# SpectrumPlusKeyboard_Kombi.net
KiCad netlist of a schematic drawn in EAGLE
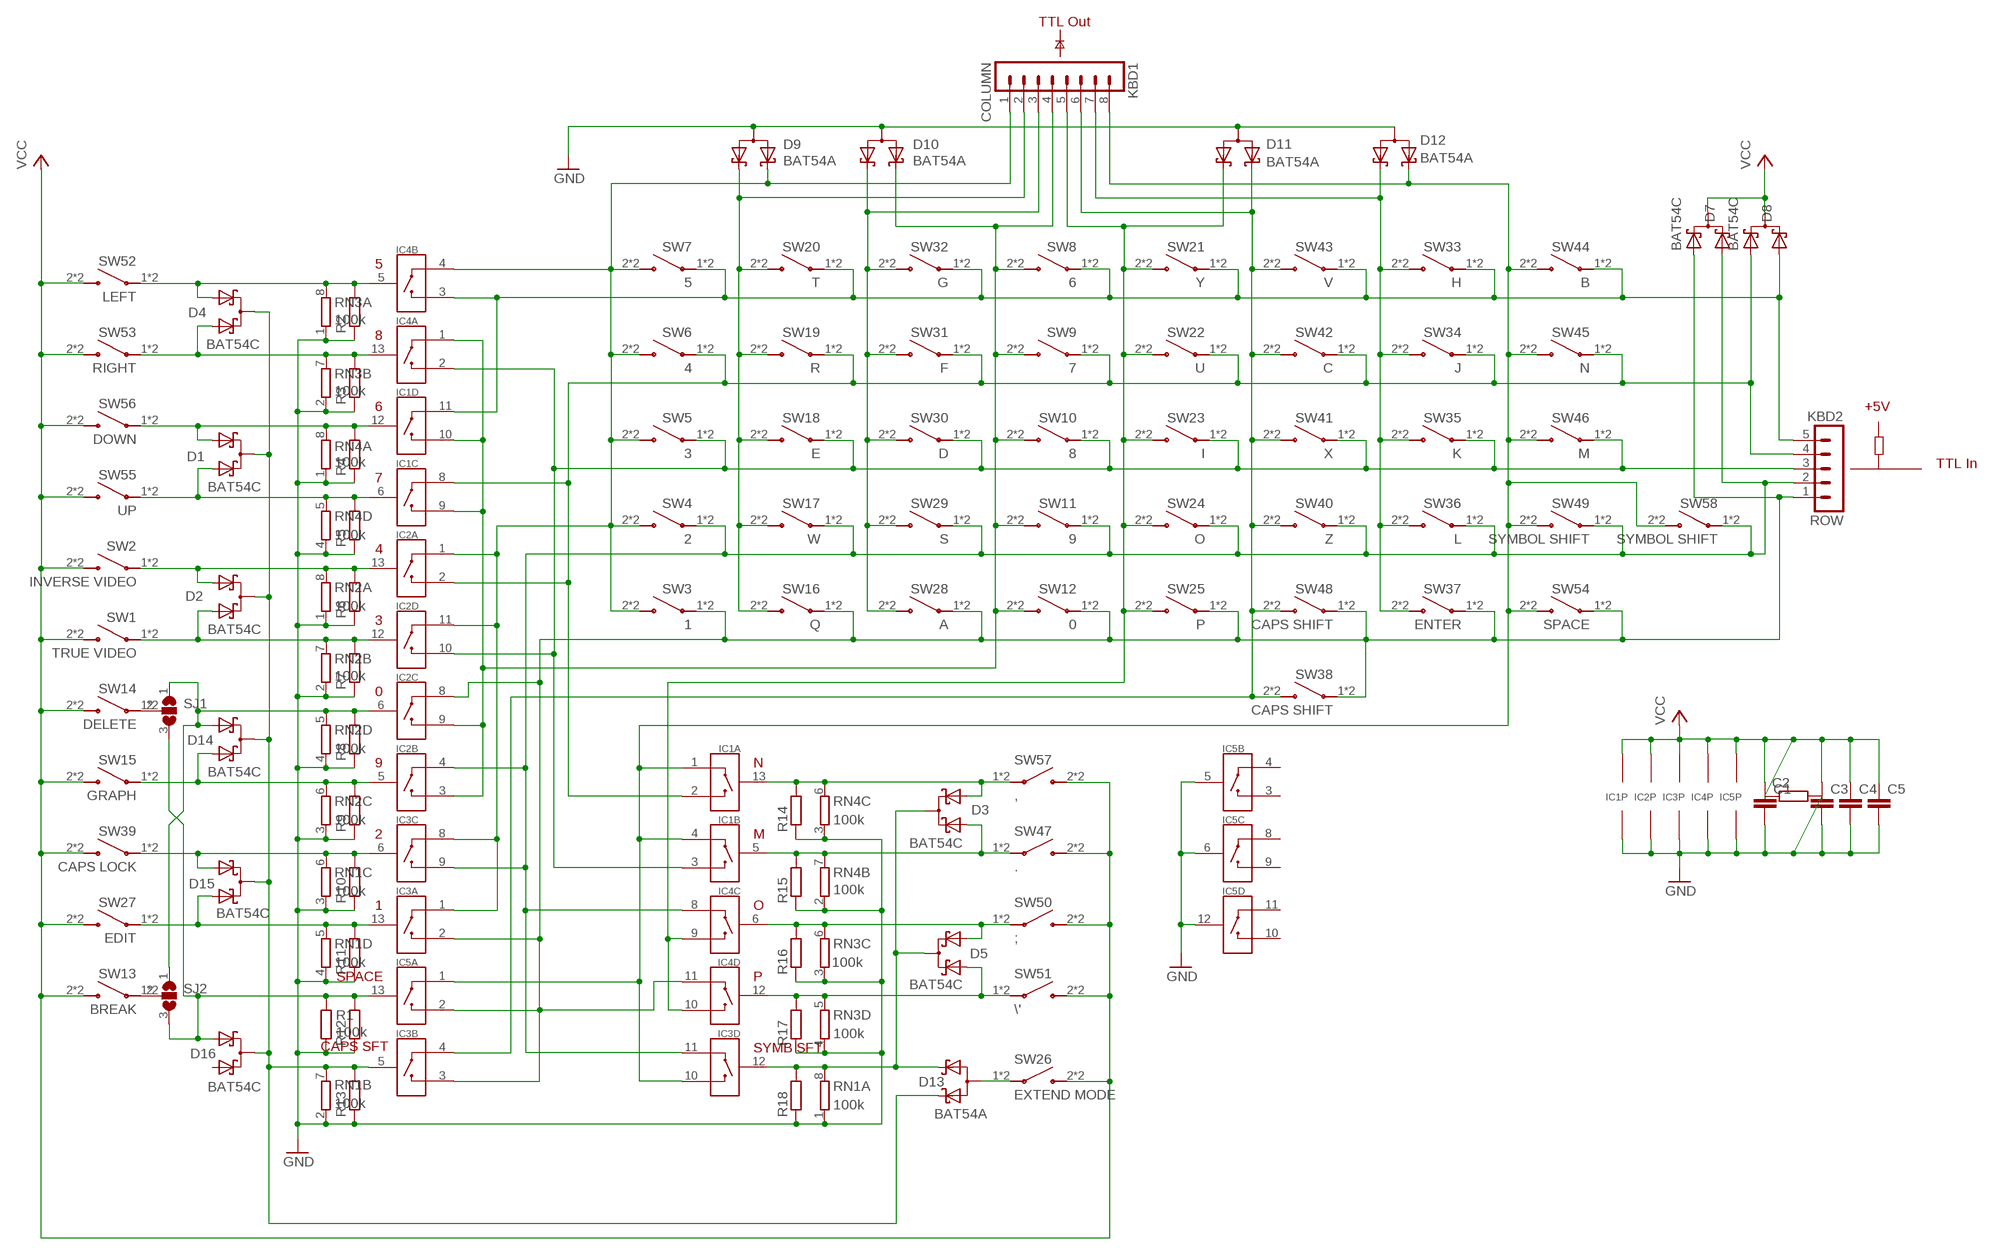
[diagram p0: schematic, sheet 1]

(export (version "E")
  (design (tool "Eeschema 10.0.6"))
  (components
    (comp (ref "C1")
      (value "C-EUC0805")
      (footprint "eagle-import:C0805")
      (libsource (lib "eagle-import") (part "C-EUC0805"))
    )
    (comp (ref "C2")
      (value "R-EU_R0805")
      (footprint "eagle-import:R0805")
      (libsource (lib "eagle-import") (part "R-EU_R0805"))
    )
    (comp (ref "C3")
      (value "C-EUC0805")
      (footprint "eagle-import:C0805")
      (libsource (lib "eagle-import") (part "C-EUC0805"))
    )
    (comp (ref "C4")
      (value "C-EUC0805")
      (footprint "eagle-import:C0805")
      (libsource (lib "eagle-import") (part "C-EUC0805"))
    )
    (comp (ref "C5")
      (value "C-EUC0805")
      (footprint "eagle-import:C0805")
      (libsource (lib "eagle-import") (part "C-EUC0805"))
    )
    (comp (ref "D1")
      (value "BAT54C")
      (footprint "eagle-import:SOT-23")
      (libsource (lib "eagle-import") (part "BAT54C"))
    )
    (comp (ref "D2")
      (value "BAT54C")
      (footprint "eagle-import:SOT-23")
      (libsource (lib "eagle-import") (part "BAT54C"))
    )
    (comp (ref "D3")
      (value "BAT54C")
      (footprint "eagle-import:SOT-23")
      (libsource (lib "eagle-import") (part "BAT54C"))
    )
    (comp (ref "D4")
      (value "BAT54C")
      (footprint "eagle-import:SOT-23")
      (libsource (lib "eagle-import") (part "BAT54C"))
    )
    (comp (ref "D5")
      (value "BAT54C")
      (footprint "eagle-import:SOT-23")
      (libsource (lib "eagle-import") (part "BAT54C"))
    )
    (comp (ref "D7")
      (value "BAT54C")
      (footprint "eagle-import:SOT-23")
      (libsource (lib "eagle-import") (part "BAT54C"))
    )
    (comp (ref "D8")
      (value "BAT54C")
      (footprint "eagle-import:SOT-23")
      (libsource (lib "eagle-import") (part "BAT54C"))
    )
    (comp (ref "D9")
      (value "BAT54A")
      (footprint "eagle-import:SOT-23")
      (libsource (lib "eagle-import") (part "BAT54A"))
    )
    (comp (ref "D10")
      (value "BAT54A")
      (footprint "eagle-import:SOT-23")
      (libsource (lib "eagle-import") (part "BAT54A"))
    )
    (comp (ref "D11")
      (value "BAT54A")
      (footprint "eagle-import:SOT-23")
      (libsource (lib "eagle-import") (part "BAT54A"))
    )
    (comp (ref "D12")
      (value "BAT54A")
      (footprint "eagle-import:SOT-23")
      (libsource (lib "eagle-import") (part "BAT54A"))
    )
    (comp (ref "D13")
      (value "BAT54A")
      (footprint "eagle-import:SOT-23")
      (libsource (lib "eagle-import") (part "BAT54A"))
    )
    (comp (ref "D14")
      (value "BAT54C")
      (footprint "eagle-import:SOT-23")
      (libsource (lib "eagle-import") (part "BAT54C"))
    )
    (comp (ref "D15")
      (value "BAT54C")
      (footprint "eagle-import:SOT-23")
      (libsource (lib "eagle-import") (part "BAT54C"))
    )
    (comp (ref "D16")
      (value "BAT54C")
      (footprint "eagle-import:SOT-23")
      (libsource (lib "eagle-import") (part "BAT54C"))
    )
    (comp (ref "IC1")
      (value "4066")
      (footprint "eagle-import:SO14")
      (libsource (lib "eagle-import") (part "4066"))
    )
    (comp (ref "IC2")
      (value "4066")
      (footprint "eagle-import:SO14")
      (libsource (lib "eagle-import") (part "4066"))
    )
    (comp (ref "IC3")
      (value "4066")
      (footprint "eagle-import:SO14")
      (libsource (lib "eagle-import") (part "4066"))
    )
    (comp (ref "IC4")
      (value "4066")
      (footprint "eagle-import:SO14")
      (libsource (lib "eagle-import") (part "4066"))
    )
    (comp (ref "IC5")
      (value "4066")
      (footprint "eagle-import:SO14")
      (libsource (lib "eagle-import") (part "4066"))
    )
    (comp (ref "KBD1")
      (value "COLUMN")
      (footprint "eagle-import:MA08-1")
      (libsource (lib "eagle-import") (part "MA08-1"))
    )
    (comp (ref "KBD2")
      (value "ROW")
      (footprint "eagle-import:MA05-1")
      (libsource (lib "eagle-import") (part "MA05-1"))
    )
    (comp (ref "R1")
      (value "100k")
      (footprint "eagle-import:R0805")
      (libsource (lib "eagle-import") (part "R-EU_R0805"))
    )
    (comp (ref "R2")
      (value "R-EU_R0805")
      (footprint "eagle-import:R0805")
      (libsource (lib "eagle-import") (part "R-EU_R0805"))
    )
    (comp (ref "R3")
      (value "R-EU_R0805")
      (footprint "eagle-import:R0805")
      (libsource (lib "eagle-import") (part "R-EU_R0805"))
    )
    (comp (ref "R4")
      (value "R-EU_R0805")
      (footprint "eagle-import:R0805")
      (libsource (lib "eagle-import") (part "R-EU_R0805"))
    )
    (comp (ref "R5")
      (value "R-EU_R0805")
      (footprint "eagle-import:R0805")
      (libsource (lib "eagle-import") (part "R-EU_R0805"))
    )
    (comp (ref "R6")
      (value "R-EU_R0805")
      (footprint "eagle-import:R0805")
      (libsource (lib "eagle-import") (part "R-EU_R0805"))
    )
    (comp (ref "R7")
      (value "R-EU_R0805")
      (footprint "eagle-import:R0805")
      (libsource (lib "eagle-import") (part "R-EU_R0805"))
    )
    (comp (ref "R8")
      (value "R-EU_R0805")
      (footprint "eagle-import:R0805")
      (libsource (lib "eagle-import") (part "R-EU_R0805"))
    )
    (comp (ref "R9")
      (value "R-EU_R0805")
      (footprint "eagle-import:R0805")
      (libsource (lib "eagle-import") (part "R-EU_R0805"))
    )
    (comp (ref "R10")
      (value "R-EU_R0805")
      (footprint "eagle-import:R0805")
      (libsource (lib "eagle-import") (part "R-EU_R0805"))
    )
    (comp (ref "R11")
      (value "R-EU_R0805")
      (footprint "eagle-import:R0805")
      (libsource (lib "eagle-import") (part "R-EU_R0805"))
    )
    (comp (ref "R12")
      (value "R-EU_R0805")
      (footprint "eagle-import:R0805")
      (libsource (lib "eagle-import") (part "R-EU_R0805"))
    )
    (comp (ref "R13")
      (value "R-EU_R0805")
      (footprint "eagle-import:R0805")
      (libsource (lib "eagle-import") (part "R-EU_R0805"))
    )
    (comp (ref "R14")
      (value "R-EU_R0805")
      (footprint "eagle-import:R0805")
      (libsource (lib "eagle-import") (part "R-EU_R0805"))
    )
    (comp (ref "R15")
      (value "R-EU_R0805")
      (footprint "eagle-import:R0805")
      (libsource (lib "eagle-import") (part "R-EU_R0805"))
    )
    (comp (ref "R16")
      (value "R-EU_R0805")
      (footprint "eagle-import:R0805")
      (libsource (lib "eagle-import") (part "R-EU_R0805"))
    )
    (comp (ref "R17")
      (value "R-EU_R0805")
      (footprint "eagle-import:R0805")
      (libsource (lib "eagle-import") (part "R-EU_R0805"))
    )
    (comp (ref "R18")
      (value "R-EU_R0805")
      (footprint "eagle-import:R0805")
      (libsource (lib "eagle-import") (part "R-EU_R0805"))
    )
    (comp (ref "RN1")
      (value "100k")
      (footprint "eagle-import:0603-ARC")
      (libsource (lib "eagle-import") (part "4R-N0603-ARC"))
    )
    (comp (ref "RN2")
      (value "100k")
      (footprint "eagle-import:0603-ARC")
      (libsource (lib "eagle-import") (part "4R-N0603-ARC"))
    )
    (comp (ref "RN3")
      (value "100k")
      (footprint "eagle-import:0603-ARC")
      (libsource (lib "eagle-import") (part "4R-N0603-ARC"))
    )
    (comp (ref "RN4")
      (value "100k")
      (footprint "eagle-import:0603-ARC")
      (libsource (lib "eagle-import") (part "4R-N0603-ARC"))
    )
    (comp (ref "SJ1")
      (value "SJ2W")
      (footprint "eagle-import:SJ_2")
      (libsource (lib "eagle-import") (part "SJ2W"))
    )
    (comp (ref "SJ2")
      (value "SJ2W")
      (footprint "eagle-import:SJ_2")
      (libsource (lib "eagle-import") (part "SJ2W"))
    )
    (comp (ref "SW1")
      (value "TRUE VIDEO")
      (footprint "eagle-import:ZX_1U_KOMBI")
      (libsource (lib "eagle-import") (part "CHERRY_MXZX_1U_KOMBI"))
    )
    (comp (ref "SW2")
      (value "INVERSE VIDEO")
      (footprint "eagle-import:ZX_1U_KOMBI")
      (libsource (lib "eagle-import") (part "CHERRY_MXZX_1U_KOMBI"))
    )
    (comp (ref "SW3")
      (value "1")
      (footprint "eagle-import:ZX_1U_KOMBI")
      (libsource (lib "eagle-import") (part "CHERRY_MXZX_1U_KOMBI"))
    )
    (comp (ref "SW4")
      (value "2")
      (footprint "eagle-import:ZX_1U_KOMBI")
      (libsource (lib "eagle-import") (part "CHERRY_MXZX_1U_KOMBI"))
    )
    (comp (ref "SW5")
      (value "3")
      (footprint "eagle-import:ZX_1U_KOMBI")
      (libsource (lib "eagle-import") (part "CHERRY_MXZX_1U_KOMBI"))
    )
    (comp (ref "SW6")
      (value "4")
      (footprint "eagle-import:ZX_1U_KOMBI")
      (libsource (lib "eagle-import") (part "CHERRY_MXZX_1U_KOMBI"))
    )
    (comp (ref "SW7")
      (value "5")
      (footprint "eagle-import:ZX_1U_KOMBI")
      (libsource (lib "eagle-import") (part "CHERRY_MXZX_1U_KOMBI"))
    )
    (comp (ref "SW8")
      (value "6")
      (footprint "eagle-import:ZX_1U_KOMBI")
      (libsource (lib "eagle-import") (part "CHERRY_MXZX_1U_KOMBI"))
    )
    (comp (ref "SW9")
      (value "7")
      (footprint "eagle-import:ZX_1U_KOMBI")
      (libsource (lib "eagle-import") (part "CHERRY_MXZX_1U_KOMBI"))
    )
    (comp (ref "SW10")
      (value "8")
      (footprint "eagle-import:ZX_1U_KOMBI")
      (libsource (lib "eagle-import") (part "CHERRY_MXZX_1U_KOMBI"))
    )
    (comp (ref "SW11")
      (value "9")
      (footprint "eagle-import:ZX_1U_KOMBI")
      (libsource (lib "eagle-import") (part "CHERRY_MXZX_1U_KOMBI"))
    )
    (comp (ref "SW12")
      (value "0")
      (footprint "eagle-import:ZX_1U_KOMBI")
      (libsource (lib "eagle-import") (part "CHERRY_MXZX_1U_KOMBI"))
    )
    (comp (ref "SW13")
      (value "BREAK")
      (footprint "eagle-import:ZX_1.5_KOMBI")
      (libsource (lib "eagle-import") (part "CHERRY_MXZX_1.5_KOMBI"))
    )
    (comp (ref "SW14")
      (value "DELETE")
      (footprint "eagle-import:ZX_1.5_KOMBI")
      (libsource (lib "eagle-import") (part "CHERRY_MXZX_1.5_KOMBI"))
    )
    (comp (ref "SW15")
      (value "GRAPH")
      (footprint "eagle-import:ZX_1U_KOMBI")
      (libsource (lib "eagle-import") (part "CHERRY_MXZX_1U_KOMBI"))
    )
    (comp (ref "SW16")
      (value "Q")
      (footprint "eagle-import:ZX_1U_KOMBI")
      (libsource (lib "eagle-import") (part "CHERRY_MXZX_1U_KOMBI"))
    )
    (comp (ref "SW17")
      (value "W")
      (footprint "eagle-import:ZX_1U_KOMBI")
      (libsource (lib "eagle-import") (part "CHERRY_MXZX_1U_KOMBI"))
    )
    (comp (ref "SW18")
      (value "E")
      (footprint "eagle-import:ZX_1U_KOMBI")
      (libsource (lib "eagle-import") (part "CHERRY_MXZX_1U_KOMBI"))
    )
    (comp (ref "SW19")
      (value "R")
      (footprint "eagle-import:ZX_1U_KOMBI")
      (libsource (lib "eagle-import") (part "CHERRY_MXZX_1U_KOMBI"))
    )
    (comp (ref "SW20")
      (value "T")
      (footprint "eagle-import:ZX_1U_KOMBI")
      (libsource (lib "eagle-import") (part "CHERRY_MXZX_1U_KOMBI"))
    )
    (comp (ref "SW21")
      (value "Y")
      (footprint "eagle-import:ZX_1U_KOMBI")
      (libsource (lib "eagle-import") (part "CHERRY_MXZX_1U_KOMBI"))
    )
    (comp (ref "SW22")
      (value "U")
      (footprint "eagle-import:ZX_1U_KOMBI")
      (libsource (lib "eagle-import") (part "CHERRY_MXZX_1U_KOMBI"))
    )
    (comp (ref "SW23")
      (value "I")
      (footprint "eagle-import:ZX_1U_KOMBI")
      (libsource (lib "eagle-import") (part "CHERRY_MXZX_1U_KOMBI"))
    )
    (comp (ref "SW24")
      (value "O")
      (footprint "eagle-import:ZX_1U_KOMBI")
      (libsource (lib "eagle-import") (part "CHERRY_MXZX_1U_KOMBI"))
    )
    (comp (ref "SW25")
      (value "P")
      (footprint "eagle-import:ZX_1U_KOMBI")
      (libsource (lib "eagle-import") (part "CHERRY_MXZX_1U_KOMBI"))
    )
    (comp (ref "SW26")
      (value "EXTEND MODE")
      (footprint "eagle-import:ZX_1.5_KOMBI")
      (libsource (lib "eagle-import") (part "CHERRY_MXZX_1.5_KOMBI"))
    )
    (comp (ref "SW27")
      (value "EDIT")
      (footprint "eagle-import:ZX_1.25U_KOMBI")
      (libsource (lib "eagle-import") (part "CHERRY_MXZX_1.25U_KOMBI"))
    )
    (comp (ref "SW28")
      (value "A")
      (footprint "eagle-import:ZX_1U_KOMBI")
      (libsource (lib "eagle-import") (part "CHERRY_MXZX_1U_KOMBI"))
    )
    (comp (ref "SW29")
      (value "S")
      (footprint "eagle-import:ZX_1U_KOMBI")
      (libsource (lib "eagle-import") (part "CHERRY_MXZX_1U_KOMBI"))
    )
    (comp (ref "SW30")
      (value "D")
      (footprint "eagle-import:ZX_1U_KOMBI")
      (libsource (lib "eagle-import") (part "CHERRY_MXZX_1U_KOMBI"))
    )
    (comp (ref "SW31")
      (value "F")
      (footprint "eagle-import:ZX_1U_KOMBI")
      (libsource (lib "eagle-import") (part "CHERRY_MXZX_1U_KOMBI"))
    )
    (comp (ref "SW32")
      (value "G")
      (footprint "eagle-import:ZX_1U_KOMBI")
      (libsource (lib "eagle-import") (part "CHERRY_MXZX_1U_KOMBI"))
    )
    (comp (ref "SW33")
      (value "H")
      (footprint "eagle-import:ZX_1U_KOMBI")
      (libsource (lib "eagle-import") (part "CHERRY_MXZX_1U_KOMBI"))
    )
    (comp (ref "SW34")
      (value "J")
      (footprint "eagle-import:ZX_1U_KOMBI")
      (libsource (lib "eagle-import") (part "CHERRY_MXZX_1U_KOMBI"))
    )
    (comp (ref "SW35")
      (value "K")
      (footprint "eagle-import:ZX_1U_KOMBI")
      (libsource (lib "eagle-import") (part "CHERRY_MXZX_1U_KOMBI"))
    )
    (comp (ref "SW36")
      (value "L")
      (footprint "eagle-import:ZX_1U_KOMBI")
      (libsource (lib "eagle-import") (part "CHERRY_MXZX_1U_KOMBI"))
    )
    (comp (ref "SW37")
      (value "ENTER")
      (footprint "eagle-import:ZX_ENTER_KOMBI")
      (libsource (lib "eagle-import") (part "CHERRY_MXZX_ENTER_KOMBI"))
    )
    (comp (ref "SW38")
      (value "CAPS SHIFT")
      (footprint "eagle-import:ZX_2.3U_KOMBI")
      (libsource (lib "eagle-import") (part "CHERRY_MXZX_2.3U_KOMBI"))
    )
    (comp (ref "SW39")
      (value "CAPS LOCK")
      (footprint "eagle-import:ZX_1U_KOMBI")
      (libsource (lib "eagle-import") (part "CHERRY_MXZX_1U_KOMBI"))
    )
    (comp (ref "SW40")
      (value "Z")
      (footprint "eagle-import:ZX_1U_KOMBI")
      (libsource (lib "eagle-import") (part "CHERRY_MXZX_1U_KOMBI"))
    )
    (comp (ref "SW41")
      (value "X")
      (footprint "eagle-import:ZX_1U_KOMBI")
      (libsource (lib "eagle-import") (part "CHERRY_MXZX_1U_KOMBI"))
    )
    (comp (ref "SW42")
      (value "C")
      (footprint "eagle-import:ZX_1U_KOMBI")
      (libsource (lib "eagle-import") (part "CHERRY_MXZX_1U_KOMBI"))
    )
    (comp (ref "SW43")
      (value "V")
      (footprint "eagle-import:ZX_1U_KOMBI")
      (libsource (lib "eagle-import") (part "CHERRY_MXZX_1U_KOMBI"))
    )
    (comp (ref "SW44")
      (value "B")
      (footprint "eagle-import:ZX_1U_KOMBI")
      (libsource (lib "eagle-import") (part "CHERRY_MXZX_1U_KOMBI"))
    )
    (comp (ref "SW45")
      (value "N")
      (footprint "eagle-import:ZX_1U_KOMBI")
      (libsource (lib "eagle-import") (part "CHERRY_MXZX_1U_KOMBI"))
    )
    (comp (ref "SW46")
      (value "M")
      (footprint "eagle-import:ZX_1U_KOMBI")
      (libsource (lib "eagle-import") (part "CHERRY_MXZX_1U_KOMBI"))
    )
    (comp (ref "SW47")
      (value ".")
      (footprint "eagle-import:ZX_1U_KOMBI")
      (libsource (lib "eagle-import") (part "CHERRY_MXZX_1U_KOMBI"))
    )
    (comp (ref "SW48")
      (value "CAPS SHIFT")
      (footprint "eagle-import:ZX_2.3U_KOMBI")
      (libsource (lib "eagle-import") (part "CHERRY_MXZX_2.3U_KOMBI"))
    )
    (comp (ref "SW49")
      (value "SYMBOL SHIFT")
      (footprint "eagle-import:ZX_1U_KOMBI")
      (libsource (lib "eagle-import") (part "CHERRY_MXZX_1U_KOMBI"))
    )
    (comp (ref "SW50")
      (value ";")
      (footprint "eagle-import:ZX_1U_KOMBI")
      (libsource (lib "eagle-import") (part "CHERRY_MXZX_1U_KOMBI"))
    )
    (comp (ref "SW51")
      (value "\\'")
      (footprint "eagle-import:ZX_1U_KOMBI")
      (libsource (lib "eagle-import") (part "CHERRY_MXZX_1U_KOMBI"))
    )
    (comp (ref "SW52")
      (value "LEFT")
      (footprint "eagle-import:ZX_1U_KOMBI")
      (libsource (lib "eagle-import") (part "CHERRY_MXZX_1U_KOMBI"))
    )
    (comp (ref "SW53")
      (value "RIGHT")
      (footprint "eagle-import:ZX_1U_KOMBI")
      (libsource (lib "eagle-import") (part "CHERRY_MXZX_1U_KOMBI"))
    )
    (comp (ref "SW54")
      (value "SPACE")
      (footprint "eagle-import:ZX_SPACE_KOMBI")
      (libsource (lib "eagle-import") (part "CHERRY_MXZX_SPACE_KOMBI"))
    )
    (comp (ref "SW55")
      (value "UP")
      (footprint "eagle-import:ZX_1U_KOMBI")
      (libsource (lib "eagle-import") (part "CHERRY_MXZX_1U_KOMBI"))
    )
    (comp (ref "SW56")
      (value "DOWN")
      (footprint "eagle-import:ZX_1U_KOMBI")
      (libsource (lib "eagle-import") (part "CHERRY_MXZX_1U_KOMBI"))
    )
    (comp (ref "SW57")
      (value ",")
      (footprint "eagle-import:ZX_1U_KOMBI")
      (libsource (lib "eagle-import") (part "CHERRY_MXZX_1U_KOMBI"))
    )
    (comp (ref "SW58")
      (value "SYMBOL SHIFT")
      (footprint "eagle-import:ZX_1U_KOMBI")
      (libsource (lib "eagle-import") (part "CHERRY_MXZX_1U_KOMBI"))
    )
  )
  (nets
    (net (code "1") (name "GND") (class "Default")
      (node (ref "C1") (pin "2") (pinfunction "2_2") (pintype "passive"))
      (node (ref "C2") (pin "2") (pinfunction "2_2") (pintype "passive"))
      (node (ref "C3") (pin "2") (pinfunction "2_2") (pintype "passive"))
      (node (ref "C4") (pin "2") (pinfunction "2_2") (pintype "passive"))
      (node (ref "C5") (pin "2") (pinfunction "2_2") (pintype "passive"))
      (node (ref "D10") (pin "3") (pinfunction "AA_3") (pintype "passive"))
      (node (ref "D11") (pin "3") (pinfunction "AA_3") (pintype "passive"))
      (node (ref "D12") (pin "3") (pinfunction "AA_3") (pintype "passive"))
      (node (ref "D9") (pin "3") (pinfunction "AA_3") (pintype "passive"))
      (node (ref "IC1") (pin "7") (pinfunction "GND_7") (pintype "power_in"))
      (node (ref "IC2") (pin "7") (pinfunction "GND_7") (pintype "power_in"))
      (node (ref "IC3") (pin "7") (pinfunction "GND_7") (pintype "power_in"))
      (node (ref "IC4") (pin "7") (pinfunction "GND_7") (pintype "power_in"))
      (node (ref "IC5") (pin "12") (pinfunction "C_12") (pintype "input"))
      (node (ref "IC5") (pin "5") (pinfunction "C_5") (pintype "input"))
      (node (ref "IC5") (pin "6") (pinfunction "C_6") (pintype "input"))
      (node (ref "IC5") (pin "7") (pinfunction "GND_7") (pintype "power_in"))
      (node (ref "R1") (pin "1") (pinfunction "1_1") (pintype "passive"))
      (node (ref "R10") (pin "1") (pinfunction "1_1") (pintype "passive"))
      (node (ref "R11") (pin "1") (pinfunction "1_1") (pintype "passive"))
      (node (ref "R12") (pin "1") (pinfunction "1_1") (pintype "passive"))
      (node (ref "R13") (pin "1") (pinfunction "1_1") (pintype "passive"))
      (node (ref "R14") (pin "1") (pinfunction "1_1") (pintype "passive"))
      (node (ref "R15") (pin "1") (pinfunction "1_1") (pintype "passive"))
      (node (ref "R16") (pin "1") (pinfunction "1_1") (pintype "passive"))
      (node (ref "R17") (pin "1") (pinfunction "1_1") (pintype "passive"))
      (node (ref "R18") (pin "1") (pinfunction "1_1") (pintype "passive"))
      (node (ref "R2") (pin "1") (pinfunction "1_1") (pintype "passive"))
      (node (ref "R3") (pin "1") (pinfunction "1_1") (pintype "passive"))
      (node (ref "R4") (pin "1") (pinfunction "1_1") (pintype "passive"))
      (node (ref "R5") (pin "1") (pinfunction "1_1") (pintype "passive"))
      (node (ref "R6") (pin "1") (pinfunction "1_1") (pintype "passive"))
      (node (ref "R7") (pin "1") (pinfunction "1_1") (pintype "passive"))
      (node (ref "R8") (pin "1") (pinfunction "1_1") (pintype "passive"))
      (node (ref "R9") (pin "1") (pinfunction "1_1") (pintype "passive"))
      (node (ref "RN1") (pin "1") (pinfunction "1_1") (pintype "passive"))
      (node (ref "RN1") (pin "2") (pinfunction "1_2") (pintype "passive"))
      (node (ref "RN1") (pin "3") (pinfunction "1_3") (pintype "passive"))
      (node (ref "RN1") (pin "4") (pinfunction "1_4") (pintype "passive"))
      (node (ref "RN2") (pin "1") (pinfunction "1_1") (pintype "passive"))
      (node (ref "RN2") (pin "2") (pinfunction "1_2") (pintype "passive"))
      (node (ref "RN2") (pin "3") (pinfunction "1_3") (pintype "passive"))
      (node (ref "RN2") (pin "4") (pinfunction "1_4") (pintype "passive"))
      (node (ref "RN3") (pin "1") (pinfunction "1_1") (pintype "passive"))
      (node (ref "RN3") (pin "2") (pinfunction "1_2") (pintype "passive"))
      (node (ref "RN3") (pin "3") (pinfunction "1_3") (pintype "passive"))
      (node (ref "RN3") (pin "4") (pinfunction "1_4") (pintype "passive"))
      (node (ref "RN4") (pin "1") (pinfunction "1_1") (pintype "passive"))
      (node (ref "RN4") (pin "2") (pinfunction "1_2") (pintype "passive"))
      (node (ref "RN4") (pin "3") (pinfunction "1_3") (pintype "passive"))
      (node (ref "RN4") (pin "4") (pinfunction "1_4") (pintype "passive"))
    )
    (net (code "2") (name "Net-(D1-A1)") (class "Default")
      (node (ref "D1") (pin "1") (pinfunction "A1_1") (pintype "passive"))
      (node (ref "IC1") (pin "12") (pinfunction "C_12") (pintype "input"))
      (node (ref "R4") (pin "2") (pinfunction "2_2") (pintype "passive"))
      (node (ref "RN4") (pin "8") (pinfunction "2_8") (pintype "passive"))
      (node (ref "SW56") (pin "1") (pinfunction "1_1") (pintype "passive"))
      (node (ref "SW56") (pin "1B") (pinfunction "1_1B") (pintype "passive"))
    )
    (net (code "3") (name "Net-(D1-A2)") (class "Default")
      (node (ref "D1") (pin "2") (pinfunction "A2_2") (pintype "passive"))
      (node (ref "IC1") (pin "6") (pinfunction "C_6") (pintype "input"))
      (node (ref "R5") (pin "2") (pinfunction "2_2") (pintype "passive"))
      (node (ref "RN4") (pin "5") (pinfunction "2_5") (pintype "passive"))
      (node (ref "SW55") (pin "1") (pinfunction "1_1") (pintype "passive"))
      (node (ref "SW55") (pin "1B") (pinfunction "1_1B") (pintype "passive"))
    )
    (net (code "4") (name "Net-(D1-CC)") (class "Default")
      (node (ref "D1") (pin "3") (pinfunction "CC_3") (pintype "passive"))
      (node (ref "D13") (pin "2") (pinfunction "K2_2") (pintype "passive"))
      (node (ref "D14") (pin "3") (pinfunction "CC_3") (pintype "passive"))
      (node (ref "D15") (pin "3") (pinfunction "CC_3") (pintype "passive"))
      (node (ref "D16") (pin "3") (pinfunction "CC_3") (pintype "passive"))
      (node (ref "D2") (pin "3") (pinfunction "CC_3") (pintype "passive"))
      (node (ref "D4") (pin "3") (pinfunction "CC_3") (pintype "passive"))
      (node (ref "IC3") (pin "5") (pinfunction "C_5") (pintype "input"))
      (node (ref "R13") (pin "2") (pinfunction "2_2") (pintype "passive"))
      (node (ref "RN1") (pin "7") (pinfunction "2_7") (pintype "passive"))
    )
    (net (code "5") (name "Net-(D2-A1)") (class "Default")
      (node (ref "D2") (pin "1") (pinfunction "A1_1") (pintype "passive"))
      (node (ref "IC2") (pin "13") (pinfunction "C_13") (pintype "input"))
      (node (ref "R6") (pin "2") (pinfunction "2_2") (pintype "passive"))
      (node (ref "RN2") (pin "8") (pinfunction "2_8") (pintype "passive"))
      (node (ref "SW2") (pin "1") (pinfunction "1_1") (pintype "passive"))
      (node (ref "SW2") (pin "1B") (pinfunction "1_1B") (pintype "passive"))
    )
    (net (code "6") (name "Net-(D2-A2)") (class "Default")
      (node (ref "D2") (pin "2") (pinfunction "A2_2") (pintype "passive"))
      (node (ref "IC2") (pin "12") (pinfunction "C_12") (pintype "input"))
      (node (ref "R7") (pin "2") (pinfunction "2_2") (pintype "passive"))
      (node (ref "RN2") (pin "7") (pinfunction "2_7") (pintype "passive"))
      (node (ref "SW1") (pin "1") (pinfunction "1_1") (pintype "passive"))
      (node (ref "SW1") (pin "1B") (pinfunction "1_1B") (pintype "passive"))
    )
    (net (code "7") (name "Net-(D3-A1)") (class "Default")
      (node (ref "D3") (pin "1") (pinfunction "A1_1") (pintype "passive"))
      (node (ref "IC1") (pin "13") (pinfunction "C_13") (pintype "input"))
      (node (ref "R14") (pin "2") (pinfunction "2_2") (pintype "passive"))
      (node (ref "RN4") (pin "6") (pinfunction "2_6") (pintype "passive"))
      (node (ref "SW57") (pin "1") (pinfunction "1_1") (pintype "passive"))
      (node (ref "SW57") (pin "1B") (pinfunction "1_1B") (pintype "passive"))
    )
    (net (code "8") (name "Net-(D3-A2)") (class "Default")
      (node (ref "D3") (pin "2") (pinfunction "A2_2") (pintype "passive"))
      (node (ref "IC1") (pin "5") (pinfunction "C_5") (pintype "input"))
      (node (ref "R15") (pin "2") (pinfunction "2_2") (pintype "passive"))
      (node (ref "RN4") (pin "7") (pinfunction "2_7") (pintype "passive"))
      (node (ref "SW47") (pin "1") (pinfunction "1_1") (pintype "passive"))
      (node (ref "SW47") (pin "1B") (pinfunction "1_1B") (pintype "passive"))
    )
    (net (code "9") (name "Net-(D4-A1)") (class "Default")
      (node (ref "D4") (pin "1") (pinfunction "A1_1") (pintype "passive"))
      (node (ref "IC4") (pin "5") (pinfunction "C_5") (pintype "input"))
      (node (ref "R2") (pin "2") (pinfunction "2_2") (pintype "passive"))
      (node (ref "RN3") (pin "8") (pinfunction "2_8") (pintype "passive"))
      (node (ref "SW52") (pin "1") (pinfunction "1_1") (pintype "passive"))
      (node (ref "SW52") (pin "1B") (pinfunction "1_1B") (pintype "passive"))
    )
    (net (code "10") (name "Net-(D4-A2)") (class "Default")
      (node (ref "D4") (pin "2") (pinfunction "A2_2") (pintype "passive"))
      (node (ref "IC4") (pin "13") (pinfunction "C_13") (pintype "input"))
      (node (ref "R3") (pin "2") (pinfunction "2_2") (pintype "passive"))
      (node (ref "RN3") (pin "7") (pinfunction "2_7") (pintype "passive"))
      (node (ref "SW53") (pin "1") (pinfunction "1_1") (pintype "passive"))
      (node (ref "SW53") (pin "1B") (pinfunction "1_1B") (pintype "passive"))
    )
    (net (code "11") (name "Net-(D5-A1)") (class "Default")
      (node (ref "D5") (pin "1") (pinfunction "A1_1") (pintype "passive"))
      (node (ref "IC4") (pin "12") (pinfunction "C_12") (pintype "input"))
      (node (ref "R17") (pin "2") (pinfunction "2_2") (pintype "passive"))
      (node (ref "RN3") (pin "5") (pinfunction "2_5") (pintype "passive"))
      (node (ref "SW51") (pin "1") (pinfunction "1_1") (pintype "passive"))
      (node (ref "SW51") (pin "1B") (pinfunction "1_1B") (pintype "passive"))
    )
    (net (code "12") (name "Net-(D5-A2)") (class "Default")
      (node (ref "D5") (pin "2") (pinfunction "A2_2") (pintype "passive"))
      (node (ref "IC4") (pin "6") (pinfunction "C_6") (pintype "input"))
      (node (ref "R16") (pin "2") (pinfunction "2_2") (pintype "passive"))
      (node (ref "RN3") (pin "6") (pinfunction "2_6") (pintype "passive"))
      (node (ref "SW50") (pin "1") (pinfunction "1_1") (pintype "passive"))
      (node (ref "SW50") (pin "1B") (pinfunction "1_1B") (pintype "passive"))
    )
    (net (code "13") (name "Net-(D7-A1)") (class "Default")
      (node (ref "D7") (pin "1") (pinfunction "A1_1") (pintype "passive"))
      (node (ref "IC2") (pin "8") (pinfunction "IO_8") (pintype "bidirectional"))
      (node (ref "IC3") (pin "2") (pinfunction "OI_2") (pintype "bidirectional"))
      (node (ref "IC3") (pin "3") (pinfunction "OI_3") (pintype "bidirectional"))
      (node (ref "IC4") (pin "11") (pinfunction "IO_11") (pintype "bidirectional"))
      (node (ref "IC5") (pin "2") (pinfunction "OI_2") (pintype "bidirectional"))
      (node (ref "KBD2") (pin "1") (pinfunction "1_1") (pintype "passive"))
      (node (ref "SW12") (pin "1") (pinfunction "1_1") (pintype "passive"))
      (node (ref "SW12") (pin "1B") (pinfunction "1_1B") (pintype "passive"))
      (node (ref "SW16") (pin "1") (pinfunction "1_1") (pintype "passive"))
      (node (ref "SW16") (pin "1B") (pinfunction "1_1B") (pintype "passive"))
      (node (ref "SW25") (pin "1") (pinfunction "1_1") (pintype "passive"))
      (node (ref "SW25") (pin "1B") (pinfunction "1_1B") (pintype "passive"))
      (node (ref "SW28") (pin "1") (pinfunction "1_1") (pintype "passive"))
      (node (ref "SW28") (pin "1B") (pinfunction "1_1B") (pintype "passive"))
      (node (ref "SW3") (pin "1") (pinfunction "1_1") (pintype "passive"))
      (node (ref "SW3") (pin "1B") (pinfunction "1_1B") (pintype "passive"))
      (node (ref "SW37") (pin "1") (pinfunction "1_1") (pintype "passive"))
      (node (ref "SW37") (pin "1B") (pinfunction "1_1B") (pintype "passive"))
      (node (ref "SW38") (pin "1") (pinfunction "1_1") (pintype "passive"))
      (node (ref "SW38") (pin "1B") (pinfunction "1_1B") (pintype "passive"))
      (node (ref "SW48") (pin "1") (pinfunction "1_1") (pintype "passive"))
      (node (ref "SW48") (pin "1B") (pinfunction "1_1B") (pintype "passive"))
      (node (ref "SW54") (pin "1") (pinfunction "1_1") (pintype "passive"))
      (node (ref "SW54") (pin "1B") (pinfunction "1_1B") (pintype "passive"))
    )
    (net (code "14") (name "Net-(D7-A2)") (class "Default")
      (node (ref "D7") (pin "2") (pinfunction "A2_2") (pintype "passive"))
      (node (ref "IC2") (pin "4") (pinfunction "IO_4") (pintype "bidirectional"))
      (node (ref "IC3") (pin "11") (pinfunction "IO_11") (pintype "bidirectional"))
      (node (ref "IC3") (pin "9") (pinfunction "OI_9") (pintype "bidirectional"))
      (node (ref "IC4") (pin "8") (pinfunction "IO_8") (pintype "bidirectional"))
      (node (ref "KBD2") (pin "2") (pinfunction "2_2") (pintype "passive"))
      (node (ref "SW11") (pin "1") (pinfunction "1_1") (pintype "passive"))
      (node (ref "SW11") (pin "1B") (pinfunction "1_1B") (pintype "passive"))
      (node (ref "SW17") (pin "1") (pinfunction "1_1") (pintype "passive"))
      (node (ref "SW17") (pin "1B") (pinfunction "1_1B") (pintype "passive"))
      (node (ref "SW24") (pin "1") (pinfunction "1_1") (pintype "passive"))
      (node (ref "SW24") (pin "1B") (pinfunction "1_1B") (pintype "passive"))
      (node (ref "SW29") (pin "1") (pinfunction "1_1") (pintype "passive"))
      (node (ref "SW29") (pin "1B") (pinfunction "1_1B") (pintype "passive"))
      (node (ref "SW36") (pin "1") (pinfunction "1_1") (pintype "passive"))
      (node (ref "SW36") (pin "1B") (pinfunction "1_1B") (pintype "passive"))
      (node (ref "SW4") (pin "1") (pinfunction "1_1") (pintype "passive"))
      (node (ref "SW4") (pin "1B") (pinfunction "1_1B") (pintype "passive"))
      (node (ref "SW40") (pin "1") (pinfunction "1_1") (pintype "passive"))
      (node (ref "SW40") (pin "1B") (pinfunction "1_1B") (pintype "passive"))
      (node (ref "SW49") (pin "1") (pinfunction "1_1") (pintype "passive"))
      (node (ref "SW49") (pin "1B") (pinfunction "1_1B") (pintype "passive"))
      (node (ref "SW58") (pin "1") (pinfunction "1_1") (pintype "passive"))
      (node (ref "SW58") (pin "1B") (pinfunction "1_1B") (pintype "passive"))
    )
    (net (code "15") (name "Net-(D8-A1)") (class "Default")
      (node (ref "D8") (pin "1") (pinfunction "A1_1") (pintype "passive"))
      (node (ref "IC1") (pin "2") (pinfunction "OI_2") (pintype "bidirectional"))
      (node (ref "IC1") (pin "8") (pinfunction "IO_8") (pintype "bidirectional"))
      (node (ref "IC2") (pin "2") (pinfunction "OI_2") (pintype "bidirectional"))
      (node (ref "KBD2") (pin "4") (pinfunction "4_4") (pintype "passive"))
      (node (ref "SW19") (pin "1") (pinfunction "1_1") (pintype "passive"))
      (node (ref "SW19") (pin "1B") (pinfunction "1_1B") (pintype "passive"))
      (node (ref "SW22") (pin "1") (pinfunction "1_1") (pintype "passive"))
      (node (ref "SW22") (pin "1B") (pinfunction "1_1B") (pintype "passive"))
      (node (ref "SW31") (pin "1") (pinfunction "1_1") (pintype "passive"))
      (node (ref "SW31") (pin "1B") (pinfunction "1_1B") (pintype "passive"))
      (node (ref "SW34") (pin "1") (pinfunction "1_1") (pintype "passive"))
      (node (ref "SW34") (pin "1B") (pinfunction "1_1B") (pintype "passive"))
      (node (ref "SW42") (pin "1") (pinfunction "1_1") (pintype "passive"))
      (node (ref "SW42") (pin "1B") (pinfunction "1_1B") (pintype "passive"))
      (node (ref "SW45") (pin "1") (pinfunction "1_1") (pintype "passive"))
      (node (ref "SW45") (pin "1B") (pinfunction "1_1B") (pintype "passive"))
      (node (ref "SW6") (pin "1") (pinfunction "1_1") (pintype "passive"))
      (node (ref "SW6") (pin "1B") (pinfunction "1_1B") (pintype "passive"))
      (node (ref "SW9") (pin "1") (pinfunction "1_1") (pintype "passive"))
      (node (ref "SW9") (pin "1B") (pinfunction "1_1B") (pintype "passive"))
    )
    (net (code "16") (name "Net-(D8-A2)") (class "Default")
      (node (ref "D8") (pin "2") (pinfunction "A2_2") (pintype "passive"))
      (node (ref "IC1") (pin "11") (pinfunction "IO_11") (pintype "bidirectional"))
      (node (ref "IC4") (pin "3") (pinfunction "OI_3") (pintype "bidirectional"))
      (node (ref "KBD2") (pin "5") (pinfunction "5_5") (pintype "passive"))
      (node (ref "SW20") (pin "1") (pinfunction "1_1") (pintype "passive"))
      (node (ref "SW20") (pin "1B") (pinfunction "1_1B") (pintype "passive"))
      (node (ref "SW21") (pin "1") (pinfunction "1_1") (pintype "passive"))
      (node (ref "SW21") (pin "1B") (pinfunction "1_1B") (pintype "passive"))
      (node (ref "SW32") (pin "1") (pinfunction "1_1") (pintype "passive"))
      (node (ref "SW32") (pin "1B") (pinfunction "1_1B") (pintype "passive"))
      (node (ref "SW33") (pin "1") (pinfunction "1_1") (pintype "passive"))
      (node (ref "SW33") (pin "1B") (pinfunction "1_1B") (pintype "passive"))
      (node (ref "SW43") (pin "1") (pinfunction "1_1") (pintype "passive"))
      (node (ref "SW43") (pin "1B") (pinfunction "1_1B") (pintype "passive"))
      (node (ref "SW44") (pin "1") (pinfunction "1_1") (pintype "passive"))
      (node (ref "SW44") (pin "1B") (pinfunction "1_1B") (pintype "passive"))
      (node (ref "SW7") (pin "1") (pinfunction "1_1") (pintype "passive"))
      (node (ref "SW7") (pin "1B") (pinfunction "1_1B") (pintype "passive"))
      (node (ref "SW8") (pin "1") (pinfunction "1_1") (pintype "passive"))
      (node (ref "SW8") (pin "1B") (pinfunction "1_1B") (pintype "passive"))
    )
    (net (code "17") (name "Net-(D9-K1)") (class "Default")
      (node (ref "D9") (pin "1") (pinfunction "K1_1") (pintype "passive"))
      (node (ref "IC2") (pin "1") (pinfunction "IO_1") (pintype "bidirectional"))
      (node (ref "IC2") (pin "11") (pinfunction "IO_11") (pintype "bidirectional"))
      (node (ref "IC3") (pin "1") (pinfunction "IO_1") (pintype "bidirectional"))
      (node (ref "IC3") (pin "8") (pinfunction "IO_8") (pintype "bidirectional"))
      (node (ref "IC4") (pin "4") (pinfunction "IO_4") (pintype "bidirectional"))
      (node (ref "KBD1") (pin "1") (pinfunction "1_1") (pintype "passive"))
      (node (ref "SW3") (pin "2") (pinfunction "2_2") (pintype "passive"))
      (node (ref "SW3") (pin "2B") (pinfunction "2_2B") (pintype "passive"))
      (node (ref "SW4") (pin "2") (pinfunction "2_2") (pintype "passive"))
      (node (ref "SW4") (pin "2B") (pinfunction "2_2B") (pintype "passive"))
      (node (ref "SW5") (pin "2") (pinfunction "2_2") (pintype "passive"))
      (node (ref "SW5") (pin "2B") (pinfunction "2_2B") (pintype "passive"))
      (node (ref "SW6") (pin "2") (pinfunction "2_2") (pintype "passive"))
      (node (ref "SW6") (pin "2B") (pinfunction "2_2B") (pintype "passive"))
      (node (ref "SW7") (pin "2") (pinfunction "2_2") (pintype "passive"))
      (node (ref "SW7") (pin "2B") (pinfunction "2_2B") (pintype "passive"))
    )
    (net (code "18") (name "Net-(D9-K2)") (class "Default")
      (node (ref "D9") (pin "2") (pinfunction "K2_2") (pintype "passive"))
      (node (ref "KBD1") (pin "2") (pinfunction "2_2") (pintype "passive"))
      (node (ref "SW16") (pin "2") (pinfunction "2_2") (pintype "passive"))
      (node (ref "SW16") (pin "2B") (pinfunction "2_2B") (pintype "passive"))
      (node (ref "SW17") (pin "2") (pinfunction "2_2") (pintype "passive"))
      (node (ref "SW17") (pin "2B") (pinfunction "2_2B") (pintype "passive"))
      (node (ref "SW18") (pin "2") (pinfunction "2_2") (pintype "passive"))
      (node (ref "SW18") (pin "2B") (pinfunction "2_2B") (pintype "passive"))
      (node (ref "SW19") (pin "2") (pinfunction "2_2") (pintype "passive"))
      (node (ref "SW19") (pin "2B") (pinfunction "2_2B") (pintype "passive"))
      (node (ref "SW20") (pin "2") (pinfunction "2_2") (pintype "passive"))
      (node (ref "SW20") (pin "2B") (pinfunction "2_2B") (pintype "passive"))
    )
    (net (code "19") (name "Net-(D10-K1)") (class "Default")
      (node (ref "D10") (pin "1") (pinfunction "K1_1") (pintype "passive"))
      (node (ref "IC1") (pin "10") (pinfunction "OI_10") (pintype "bidirectional"))
      (node (ref "IC1") (pin "9") (pinfunction "OI_9") (pintype "bidirectional"))
      (node (ref "IC2") (pin "3") (pinfunction "OI_3") (pintype "bidirectional"))
      (node (ref "IC2") (pin "9") (pinfunction "OI_9") (pintype "bidirectional"))
      (node (ref "IC4") (pin "1") (pinfunction "IO_1") (pintype "bidirectional"))
      (node (ref "KBD1") (pin "4") (pinfunction "4_4") (pintype "passive"))
      (node (ref "SW10") (pin "2") (pinfunction "2_2") (pintype "passive"))
      (node (ref "SW10") (pin "2B") (pinfunction "2_2B") (pintype "passive"))
      (node (ref "SW11") (pin "2") (pinfunction "2_2") (pintype "passive"))
      (node (ref "SW11") (pin "2B") (pinfunction "2_2B") (pintype "passive"))
      (node (ref "SW12") (pin "2") (pinfunction "2_2") (pintype "passive"))
      (node (ref "SW12") (pin "2B") (pinfunction "2_2B") (pintype "passive"))
      (node (ref "SW8") (pin "2") (pinfunction "2_2") (pintype "passive"))
      (node (ref "SW8") (pin "2B") (pinfunction "2_2B") (pintype "passive"))
      (node (ref "SW9") (pin "2") (pinfunction "2_2") (pintype "passive"))
      (node (ref "SW9") (pin "2B") (pinfunction "2_2B") (pintype "passive"))
    )
    (net (code "20") (name "Net-(D10-K2)") (class "Default")
      (node (ref "D10") (pin "2") (pinfunction "K2_2") (pintype "passive"))
      (node (ref "KBD1") (pin "3") (pinfunction "3_3") (pintype "passive"))
      (node (ref "SW28") (pin "2") (pinfunction "2_2") (pintype "passive"))
      (node (ref "SW28") (pin "2B") (pinfunction "2_2B") (pintype "passive"))
      (node (ref "SW29") (pin "2") (pinfunction "2_2") (pintype "passive"))
      (node (ref "SW29") (pin "2B") (pinfunction "2_2B") (pintype "passive"))
      (node (ref "SW30") (pin "2") (pinfunction "2_2") (pintype "passive"))
      (node (ref "SW30") (pin "2B") (pinfunction "2_2B") (pintype "passive"))
      (node (ref "SW31") (pin "2") (pinfunction "2_2") (pintype "passive"))
      (node (ref "SW31") (pin "2B") (pinfunction "2_2B") (pintype "passive"))
      (node (ref "SW32") (pin "2") (pinfunction "2_2") (pintype "passive"))
      (node (ref "SW32") (pin "2B") (pinfunction "2_2B") (pintype "passive"))
    )
    (net (code "21") (name "Net-(D11-K1)") (class "Default")
      (node (ref "D11") (pin "1") (pinfunction "K1_1") (pintype "passive"))
      (node (ref "IC4") (pin "10") (pinfunction "OI_10") (pintype "bidirectional"))
      (node (ref "IC4") (pin "9") (pinfunction "OI_9") (pintype "bidirectional"))
      (node (ref "KBD1") (pin "5") (pinfunction "5_5") (pintype "passive"))
      (node (ref "SW21") (pin "2") (pinfunction "2_2") (pintype "passive"))
      (node (ref "SW21") (pin "2B") (pinfunction "2_2B") (pintype "passive"))
      (node (ref "SW22") (pin "2") (pinfunction "2_2") (pintype "passive"))
      (node (ref "SW22") (pin "2B") (pinfunction "2_2B") (pintype "passive"))
      (node (ref "SW23") (pin "2") (pinfunction "2_2") (pintype "passive"))
      (node (ref "SW23") (pin "2B") (pinfunction "2_2B") (pintype "passive"))
      (node (ref "SW24") (pin "2") (pinfunction "2_2") (pintype "passive"))
      (node (ref "SW24") (pin "2B") (pinfunction "2_2B") (pintype "passive"))
      (node (ref "SW25") (pin "2") (pinfunction "2_2") (pintype "passive"))
      (node (ref "SW25") (pin "2B") (pinfunction "2_2B") (pintype "passive"))
    )
    (net (code "22") (name "Net-(D11-K2)") (class "Default")
      (node (ref "D11") (pin "2") (pinfunction "K2_2") (pintype "passive"))
      (node (ref "IC3") (pin "4") (pinfunction "IO_4") (pintype "bidirectional"))
      (node (ref "KBD1") (pin "6") (pinfunction "6_6") (pintype "passive"))
      (node (ref "SW38") (pin "2") (pinfunction "2_2") (pintype "passive"))
      (node (ref "SW38") (pin "2B") (pinfunction "2_2B") (pintype "passive"))
      (node (ref "SW40") (pin "2") (pinfunction "2_2") (pintype "passive"))
      (node (ref "SW40") (pin "2B") (pinfunction "2_2B") (pintype "passive"))
      (node (ref "SW41") (pin "2") (pinfunction "2_2") (pintype "passive"))
      (node (ref "SW41") (pin "2B") (pinfunction "2_2B") (pintype "passive"))
      (node (ref "SW42") (pin "2") (pinfunction "2_2") (pintype "passive"))
      (node (ref "SW42") (pin "2B") (pinfunction "2_2B") (pintype "passive"))
      (node (ref "SW43") (pin "2") (pinfunction "2_2") (pintype "passive"))
      (node (ref "SW43") (pin "2B") (pinfunction "2_2B") (pintype "passive"))
      (node (ref "SW48") (pin "2") (pinfunction "2_2") (pintype "passive"))
      (node (ref "SW48") (pin "2B") (pinfunction "2_2B") (pintype "passive"))
    )
    (net (code "23") (name "Net-(D12-K1)") (class "Default")
      (node (ref "D12") (pin "1") (pinfunction "K1_1") (pintype "passive"))
      (node (ref "IC1") (pin "1") (pinfunction "IO_1") (pintype "bidirectional"))
      (node (ref "IC1") (pin "4") (pinfunction "IO_4") (pintype "bidirectional"))
      (node (ref "IC3") (pin "10") (pinfunction "OI_10") (pintype "bidirectional"))
      (node (ref "IC5") (pin "1") (pinfunction "IO_1") (pintype "bidirectional"))
      (node (ref "KBD1") (pin "8") (pinfunction "8_8") (pintype "passive"))
      (node (ref "SW44") (pin "2") (pinfunction "2_2") (pintype "passive"))
      (node (ref "SW44") (pin "2B") (pinfunction "2_2B") (pintype "passive"))
      (node (ref "SW45") (pin "2") (pinfunction "2_2") (pintype "passive"))
      (node (ref "SW45") (pin "2B") (pinfunction "2_2B") (pintype "passive"))
      (node (ref "SW46") (pin "2") (pinfunction "2_2") (pintype "passive"))
      (node (ref "SW46") (pin "2B") (pinfunction "2_2B") (pintype "passive"))
      (node (ref "SW49") (pin "2") (pinfunction "2_2") (pintype "passive"))
      (node (ref "SW49") (pin "2B") (pinfunction "2_2B") (pintype "passive"))
      (node (ref "SW54") (pin "2") (pinfunction "2_2") (pintype "passive"))
      (node (ref "SW54") (pin "2B") (pinfunction "2_2B") (pintype "passive"))
      (node (ref "SW58") (pin "2") (pinfunction "2_2") (pintype "passive"))
      (node (ref "SW58") (pin "2B") (pinfunction "2_2B") (pintype "passive"))
    )
    (net (code "24") (name "Net-(D12-K2)") (class "Default")
      (node (ref "D12") (pin "2") (pinfunction "K2_2") (pintype "passive"))
      (node (ref "KBD1") (pin "7") (pinfunction "7_7") (pintype "passive"))
      (node (ref "SW33") (pin "2") (pinfunction "2_2") (pintype "passive"))
      (node (ref "SW33") (pin "2B") (pinfunction "2_2B") (pintype "passive"))
      (node (ref "SW34") (pin "2") (pinfunction "2_2") (pintype "passive"))
      (node (ref "SW34") (pin "2B") (pinfunction "2_2B") (pintype "passive"))
      (node (ref "SW35") (pin "2") (pinfunction "2_2") (pintype "passive"))
      (node (ref "SW35") (pin "2B") (pinfunction "2_2B") (pintype "passive"))
      (node (ref "SW36") (pin "2") (pinfunction "2_2") (pintype "passive"))
      (node (ref "SW36") (pin "2B") (pinfunction "2_2B") (pintype "passive"))
      (node (ref "SW37") (pin "2") (pinfunction "2_2") (pintype "passive"))
      (node (ref "SW37") (pin "2B") (pinfunction "2_2B") (pintype "passive"))
    )
    (net (code "25") (name "Net-(D13-AA)") (class "Default")
      (node (ref "D13") (pin "3") (pinfunction "AA_3") (pintype "passive"))
      (node (ref "SW26") (pin "1") (pinfunction "1_1") (pintype "passive"))
      (node (ref "SW26") (pin "1B") (pinfunction "1_1B") (pintype "passive"))
    )
    (net (code "26") (name "Net-(D13-K1)") (class "Default")
      (node (ref "D13") (pin "1") (pinfunction "K1_1") (pintype "passive"))
      (node (ref "D3") (pin "3") (pinfunction "CC_3") (pintype "passive"))
      (node (ref "D5") (pin "3") (pinfunction "CC_3") (pintype "passive"))
      (node (ref "IC3") (pin "12") (pinfunction "C_12") (pintype "input"))
      (node (ref "R18") (pin "2") (pinfunction "2_2") (pintype "passive"))
      (node (ref "RN1") (pin "8") (pinfunction "2_8") (pintype "passive"))
    )
    (net (code "27") (name "Net-(D14-A1)") (class "Default")
      (node (ref "D14") (pin "1") (pinfunction "A1_1") (pintype "passive"))
      (node (ref "IC2") (pin "6") (pinfunction "C_6") (pintype "input"))
      (node (ref "R8") (pin "2") (pinfunction "2_2") (pintype "passive"))
      (node (ref "RN2") (pin "5") (pinfunction "2_5") (pintype "passive"))
      (node (ref "SJ1") (pin "1") (pinfunction "1_1") (pintype "passive"))
      (node (ref "SJ2") (pin "1") (pinfunction "1_1") (pintype "passive"))
    )
    (net (code "28") (name "Net-(D14-A2)") (class "Default")
      (node (ref "D14") (pin "2") (pinfunction "A2_2") (pintype "passive"))
      (node (ref "IC2") (pin "5") (pinfunction "C_5") (pintype "input"))
      (node (ref "R9") (pin "2") (pinfunction "2_2") (pintype "passive"))
      (node (ref "RN2") (pin "6") (pinfunction "2_6") (pintype "passive"))
      (node (ref "SW15") (pin "1") (pinfunction "1_1") (pintype "passive"))
      (node (ref "SW15") (pin "1B") (pinfunction "1_1B") (pintype "passive"))
    )
    (net (code "29") (name "Net-(D15-A1)") (class "Default")
      (node (ref "D15") (pin "1") (pinfunction "A1_1") (pintype "passive"))
      (node (ref "IC3") (pin "13") (pinfunction "C_13") (pintype "input"))
      (node (ref "R11") (pin "2") (pinfunction "2_2") (pintype "passive"))
      (node (ref "RN1") (pin "5") (pinfunction "2_5") (pintype "passive"))
      (node (ref "SW27") (pin "1") (pinfunction "1_1") (pintype "passive"))
      (node (ref "SW27") (pin "1B") (pinfunction "1_1B") (pintype "passive"))
    )
    (net (code "30") (name "Net-(D15-A2)") (class "Default")
      (node (ref "D15") (pin "2") (pinfunction "A2_2") (pintype "passive"))
      (node (ref "IC3") (pin "6") (pinfunction "C_6") (pintype "input"))
      (node (ref "R10") (pin "2") (pinfunction "2_2") (pintype "passive"))
      (node (ref "RN1") (pin "6") (pinfunction "2_6") (pintype "passive"))
      (node (ref "SW39") (pin "1") (pinfunction "1_1") (pintype "passive"))
      (node (ref "SW39") (pin "1B") (pinfunction "1_1B") (pintype "passive"))
    )
    (net (code "31") (name "Net-(D16-A1)") (class "Default")
      (node (ref "D16") (pin "1") (pinfunction "A1_1") (pintype "passive"))
      (node (ref "IC5") (pin "13") (pinfunction "C_13") (pintype "input"))
      (node (ref "R1") (pin "2") (pinfunction "2_2") (pintype "passive"))
      (node (ref "R12") (pin "2") (pinfunction "2_2") (pintype "passive"))
      (node (ref "SJ1") (pin "3") (pinfunction "3_3") (pintype "passive"))
      (node (ref "SJ2") (pin "3") (pinfunction "3_3") (pintype "passive"))
    )
    (net (code "32") (name "Net-(IC1B-OI)") (class "Default")
      (node (ref "IC1") (pin "3") (pinfunction "OI_3") (pintype "bidirectional"))
      (node (ref "IC2") (pin "10") (pinfunction "OI_10") (pintype "bidirectional"))
      (node (ref "IC4") (pin "2") (pinfunction "OI_2") (pintype "bidirectional"))
      (node (ref "KBD2") (pin "3") (pinfunction "3_3") (pintype "passive"))
      (node (ref "SW10") (pin "1") (pinfunction "1_1") (pintype "passive"))
      (node (ref "SW10") (pin "1B") (pinfunction "1_1B") (pintype "passive"))
      (node (ref "SW18") (pin "1") (pinfunction "1_1") (pintype "passive"))
      (node (ref "SW18") (pin "1B") (pinfunction "1_1B") (pintype "passive"))
      (node (ref "SW23") (pin "1") (pinfunction "1_1") (pintype "passive"))
      (node (ref "SW23") (pin "1B") (pinfunction "1_1B") (pintype "passive"))
      (node (ref "SW30") (pin "1") (pinfunction "1_1") (pintype "passive"))
      (node (ref "SW30") (pin "1B") (pinfunction "1_1B") (pintype "passive"))
      (node (ref "SW35") (pin "1") (pinfunction "1_1") (pintype "passive"))
      (node (ref "SW35") (pin "1B") (pinfunction "1_1B") (pintype "passive"))
      (node (ref "SW41") (pin "1") (pinfunction "1_1") (pintype "passive"))
      (node (ref "SW41") (pin "1B") (pinfunction "1_1B") (pintype "passive"))
      (node (ref "SW46") (pin "1") (pinfunction "1_1") (pintype "passive"))
      (node (ref "SW46") (pin "1B") (pinfunction "1_1B") (pintype "passive"))
      (node (ref "SW5") (pin "1") (pinfunction "1_1") (pintype "passive"))
      (node (ref "SW5") (pin "1B") (pinfunction "1_1B") (pintype "passive"))
    )
    (net (code "33") (name "Net-(SJ1-Pad2)") (class "Default")
      (node (ref "SJ1") (pin "2") (pinfunction "2_2") (pintype "passive"))
      (node (ref "SW14") (pin "1") (pinfunction "1_1") (pintype "passive"))
      (node (ref "SW14") (pin "1B") (pinfunction "1_1B") (pintype "passive"))
    )
    (net (code "34") (name "Net-(SJ2-Pad2)") (class "Default")
      (node (ref "SJ2") (pin "2") (pinfunction "2_2") (pintype "passive"))
      (node (ref "SW13") (pin "1") (pinfunction "1_1") (pintype "passive"))
      (node (ref "SW13") (pin "1B") (pinfunction "1_1B") (pintype "passive"))
    )
    (net (code "35") (name "VCC") (class "Default")
      (node (ref "C1") (pin "1") (pinfunction "1_1") (pintype "passive"))
      (node (ref "C2") (pin "1") (pinfunction "1_1") (pintype "passive"))
      (node (ref "C3") (pin "1") (pinfunction "1_1") (pintype "passive"))
      (node (ref "C4") (pin "1") (pinfunction "1_1") (pintype "passive"))
      (node (ref "C5") (pin "1") (pinfunction "1_1") (pintype "passive"))
      (node (ref "D7") (pin "3") (pinfunction "CC_3") (pintype "passive"))
      (node (ref "D8") (pin "3") (pinfunction "CC_3") (pintype "passive"))
      (node (ref "IC1") (pin "14") (pinfunction "VCC_14") (pintype "power_in"))
      (node (ref "IC2") (pin "14") (pinfunction "VCC_14") (pintype "power_in"))
      (node (ref "IC3") (pin "14") (pinfunction "VCC_14") (pintype "power_in"))
      (node (ref "IC4") (pin "14") (pinfunction "VCC_14") (pintype "power_in"))
      (node (ref "IC5") (pin "14") (pinfunction "VCC_14") (pintype "power_in"))
      (node (ref "SW1") (pin "2") (pinfunction "2_2") (pintype "passive"))
      (node (ref "SW1") (pin "2B") (pinfunction "2_2B") (pintype "passive"))
      (node (ref "SW13") (pin "2") (pinfunction "2_2") (pintype "passive"))
      (node (ref "SW13") (pin "2B") (pinfunction "2_2B") (pintype "passive"))
      (node (ref "SW14") (pin "2") (pinfunction "2_2") (pintype "passive"))
      (node (ref "SW14") (pin "2B") (pinfunction "2_2B") (pintype "passive"))
      (node (ref "SW15") (pin "2") (pinfunction "2_2") (pintype "passive"))
      (node (ref "SW15") (pin "2B") (pinfunction "2_2B") (pintype "passive"))
      (node (ref "SW2") (pin "2") (pinfunction "2_2") (pintype "passive"))
      (node (ref "SW2") (pin "2B") (pinfunction "2_2B") (pintype "passive"))
      (node (ref "SW26") (pin "2") (pinfunction "2_2") (pintype "passive"))
      (node (ref "SW26") (pin "2B") (pinfunction "2_2B") (pintype "passive"))
      (node (ref "SW27") (pin "2") (pinfunction "2_2") (pintype "passive"))
      (node (ref "SW27") (pin "2B") (pinfunction "2_2B") (pintype "passive"))
      (node (ref "SW39") (pin "2") (pinfunction "2_2") (pintype "passive"))
      (node (ref "SW39") (pin "2B") (pinfunction "2_2B") (pintype "passive"))
      (node (ref "SW47") (pin "2") (pinfunction "2_2") (pintype "passive"))
      (node (ref "SW47") (pin "2B") (pinfunction "2_2B") (pintype "passive"))
      (node (ref "SW50") (pin "2") (pinfunction "2_2") (pintype "passive"))
      (node (ref "SW50") (pin "2B") (pinfunction "2_2B") (pintype "passive"))
      (node (ref "SW51") (pin "2") (pinfunction "2_2") (pintype "passive"))
      (node (ref "SW51") (pin "2B") (pinfunction "2_2B") (pintype "passive"))
      (node (ref "SW52") (pin "2") (pinfunction "2_2") (pintype "passive"))
      (node (ref "SW52") (pin "2B") (pinfunction "2_2B") (pintype "passive"))
      (node (ref "SW53") (pin "2") (pinfunction "2_2") (pintype "passive"))
      (node (ref "SW53") (pin "2B") (pinfunction "2_2B") (pintype "passive"))
      (node (ref "SW55") (pin "2") (pinfunction "2_2") (pintype "passive"))
      (node (ref "SW55") (pin "2B") (pinfunction "2_2B") (pintype "passive"))
      (node (ref "SW56") (pin "2") (pinfunction "2_2") (pintype "passive"))
      (node (ref "SW56") (pin "2B") (pinfunction "2_2B") (pintype "passive"))
      (node (ref "SW57") (pin "2") (pinfunction "2_2") (pintype "passive"))
      (node (ref "SW57") (pin "2B") (pinfunction "2_2B") (pintype "passive"))
    )
    (net (code "36") (name "unconnected-(D16-A2-Pad2)") (class "Default")
      (node (ref "D16") (pin "2") (pinfunction "A2_2") (pintype "passive"))
    )
    (net (code "37") (name "unconnected-(IC5B-IO-Pad4)") (class "Default")
      (node (ref "IC5") (pin "4") (pinfunction "IO_4") (pintype "bidirectional"))
    )
    (net (code "38") (name "unconnected-(IC5B-OI-Pad3)") (class "Default")
      (node (ref "IC5") (pin "3") (pinfunction "OI_3") (pintype "bidirectional"))
    )
    (net (code "39") (name "unconnected-(IC5C-IO-Pad8)") (class "Default")
      (node (ref "IC5") (pin "8") (pinfunction "IO_8") (pintype "bidirectional"))
    )
    (net (code "40") (name "unconnected-(IC5C-OI-Pad9)") (class "Default")
      (node (ref "IC5") (pin "9") (pinfunction "OI_9") (pintype "bidirectional"))
    )
    (net (code "41") (name "unconnected-(IC5D-IO-Pad11)") (class "Default")
      (node (ref "IC5") (pin "11") (pinfunction "IO_11") (pintype "bidirectional"))
    )
    (net (code "42") (name "unconnected-(IC5D-OI-Pad10)") (class "Default")
      (node (ref "IC5") (pin "10") (pinfunction "OI_10") (pintype "bidirectional"))
    )
  )
)
